# AD_IanFritz_CONTROLS.net
KiCad netlist of a schematic drawn in EAGLE
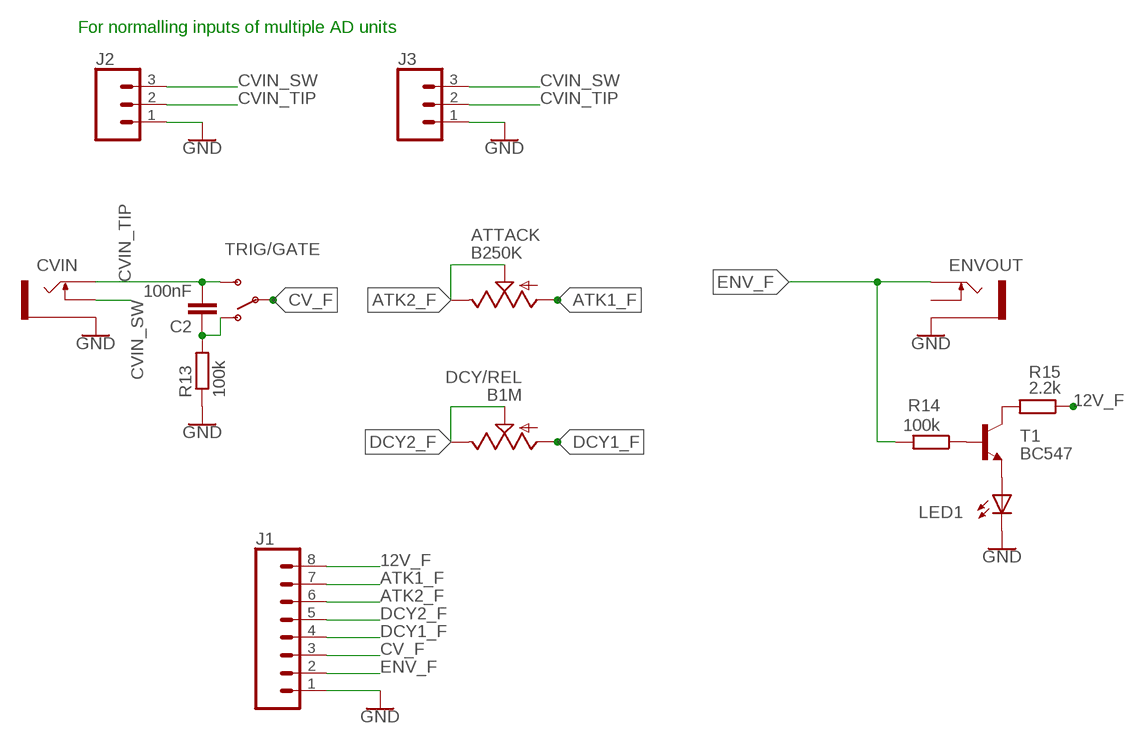
[diagram p0: schematic, sheet 1]

(export (version "E")
  (design (tool "Eeschema 10.0.6"))
  (components
    (comp (ref "ATTACK")
      (value "B250K")
      (footprint "eagle-import:9MM_SNAP-IN_POT")
      (libsource (lib "eagle-import") (part "9MM_SNAP-IN_POT_"))
    )
    (comp (ref "C2")
      (value "100nF")
      (footprint "eagle-import:C2.5-3")
      (libsource (lib "eagle-import") (part "C2,5-3"))
    )
    (comp (ref "CVIN")
      (value "THONKICONNNEW")
      (footprint "eagle-import:WQP-PJ301M-12_JACK")
      (libsource (lib "eagle-import") (part "THONKICONNNEW"))
    )
    (comp (ref "DCY/REL")
      (value "B1M")
      (footprint "eagle-import:9MM_SNAP-IN_POT")
      (libsource (lib "eagle-import") (part "9MM_SNAP-IN_POT_"))
    )
    (comp (ref "ENVOUT")
      (value "THONKICONNNEW")
      (footprint "eagle-import:WQP-PJ301M-12_JACK")
      (libsource (lib "eagle-import") (part "THONKICONNNEW"))
    )
    (comp (ref "J1")
      (value "CONN_08\"")
      (footprint "eagle-import:1X08")
      (libsource (lib "eagle-import") (part "CONN_08{dblquote}"))
    )
    (comp (ref "J2")
      (value "CONN_031X03_NO_SILK")
      (footprint "eagle-import:1X03_NO_SILK")
      (libsource (lib "eagle-import") (part "CONN_031X03_NO_SILK"))
    )
    (comp (ref "J3")
      (value "CONN_031X03_NO_SILK")
      (footprint "eagle-import:1X03_NO_SILK")
      (libsource (lib "eagle-import") (part "CONN_031X03_NO_SILK"))
    )
    (comp (ref "LED1")
      (value "LED3MM")
      (footprint "eagle-import:LED3MM")
      (libsource (lib "eagle-import") (part "LED3MM"))
    )
    (comp (ref "R13")
      (value "100k")
      (footprint "eagle-import:7MM_RESISTOR")
      (libsource (lib "eagle-import") (part "RESISTOR7MM"))
    )
    (comp (ref "R14")
      (value "100k")
      (footprint "eagle-import:7MM_RESISTOR")
      (libsource (lib "eagle-import") (part "RESISTOR7MM"))
    )
    (comp (ref "R15")
      (value "2.2k")
      (footprint "eagle-import:7MM_RESISTOR")
      (libsource (lib "eagle-import") (part "RESISTOR7MM"))
    )
    (comp (ref "T1")
      (value "BC547")
      (footprint "eagle-import:TO92")
      (libsource (lib "eagle-import") (part "BC547"))
    )
    (comp (ref "TRIG/GATE")
      (value "SUBMINI_SPDT")
      (footprint "eagle-import:SUBMINI_TOGGLE")
      (libsource (lib "eagle-import") (part "SUBMINI_SPDT"))
    )
  )
  (nets
    (net (code "1") (name "/12V_F") (class "Default")
      (node (ref "J1") (pin "8") (pinfunction "8_8") (pintype "passive"))
      (node (ref "R15") (pin "1") (pinfunction "1_1") (pintype "passive"))
    )
    (net (code "2") (name "/CVIN_SW") (class "Default")
      (node (ref "CVIN") (pin "P$2_SWITCH") (pinfunction "SWITCH_P$2_SWITCH") (pintype "passive"))
      (node (ref "J2") (pin "3") (pinfunction "3_3") (pintype "passive"))
      (node (ref "J3") (pin "3") (pinfunction "3_3") (pintype "passive"))
    )
    (net (code "3") (name "/CVIN_TIP") (class "Default")
      (node (ref "C2") (pin "2") (pinfunction "2_2") (pintype "passive"))
      (node (ref "CVIN") (pin "P$1_TIP") (pinfunction "TIP_P$1_TIP") (pintype "passive"))
      (node (ref "J2") (pin "2") (pinfunction "2_2") (pintype "passive"))
      (node (ref "J3") (pin "2") (pinfunction "2_2") (pintype "passive"))
      (node (ref "TRIG/GATE") (pin "3") (pinfunction "S_3") (pintype "passive"))
    )
    (net (code "4") (name "ATK1_F") (class "Default")
      (node (ref "ATTACK") (pin "1") (pinfunction "A_1") (pintype "passive"))
      (node (ref "J1") (pin "7") (pinfunction "7_7") (pintype "passive"))
    )
    (net (code "5") (name "ATK2_F") (class "Default")
      (node (ref "ATTACK") (pin "2") (pinfunction "S_2") (pintype "passive"))
      (node (ref "ATTACK") (pin "3") (pinfunction "E_3") (pintype "passive"))
      (node (ref "J1") (pin "6") (pinfunction "6_6") (pintype "passive"))
    )
    (net (code "6") (name "CV_F") (class "Default")
      (node (ref "J1") (pin "3") (pinfunction "3_3") (pintype "passive"))
      (node (ref "TRIG/GATE") (pin "COM") (pinfunction "COMMON_COM") (pintype "passive"))
    )
    (net (code "7") (name "DCY1_F") (class "Default")
      (node (ref "DCY/REL") (pin "1") (pinfunction "A_1") (pintype "passive"))
      (node (ref "J1") (pin "4") (pinfunction "4_4") (pintype "passive"))
    )
    (net (code "8") (name "DCY2_F") (class "Default")
      (node (ref "DCY/REL") (pin "2") (pinfunction "S_2") (pintype "passive"))
      (node (ref "DCY/REL") (pin "3") (pinfunction "E_3") (pintype "passive"))
      (node (ref "J1") (pin "5") (pinfunction "5_5") (pintype "passive"))
    )
    (net (code "9") (name "ENV_F") (class "Default")
      (node (ref "ENVOUT") (pin "P$1_TIP") (pinfunction "TIP_P$1_TIP") (pintype "passive"))
      (node (ref "J1") (pin "2") (pinfunction "2_2") (pintype "passive"))
      (node (ref "R14") (pin "2") (pinfunction "2_2") (pintype "passive"))
    )
    (net (code "10") (name "GND") (class "Default")
      (node (ref "CVIN") (pin "P$3_SLEEVE") (pinfunction "SLEEVE_P$3_SLEEVE") (pintype "passive"))
      (node (ref "ENVOUT") (pin "P$3_SLEEVE") (pinfunction "SLEEVE_P$3_SLEEVE") (pintype "passive"))
      (node (ref "J1") (pin "1") (pinfunction "1_1") (pintype "passive"))
      (node (ref "J2") (pin "1") (pinfunction "1_1") (pintype "passive"))
      (node (ref "J3") (pin "1") (pinfunction "1_1") (pintype "passive"))
      (node (ref "LED1") (pin "K") (pinfunction "C_K") (pintype "passive"))
      (node (ref "R13") (pin "1") (pinfunction "1_1") (pintype "passive"))
    )
    (net (code "11") (name "Net-(T1-B)") (class "Default")
      (node (ref "R14") (pin "1") (pinfunction "1_1") (pintype "passive"))
      (node (ref "T1") (pin "2") (pinfunction "B_2") (pintype "passive"))
    )
    (net (code "12") (name "Net-(T1-C)") (class "Default")
      (node (ref "R15") (pin "2") (pinfunction "2_2") (pintype "passive"))
      (node (ref "T1") (pin "3") (pinfunction "C_3") (pintype "passive"))
    )
    (net (code "13") (name "Net-(T1-E)") (class "Default")
      (node (ref "LED1") (pin "A") (pinfunction "A_A") (pintype "passive"))
      (node (ref "T1") (pin "1") (pinfunction "E_1") (pintype "passive"))
    )
    (net (code "14") (name "Net-(TRIG/GATE-O)") (class "Default")
      (node (ref "C2") (pin "1") (pinfunction "1_1") (pintype "passive"))
      (node (ref "R13") (pin "2") (pinfunction "2_2") (pintype "passive"))
      (node (ref "TRIG/GATE") (pin "1") (pinfunction "O_1") (pintype "passive"))
    )
    (net (code "15") (name "unconnected-(ENVOUT-SWITCH-PadP$2_SWITCH)") (class "Default")
      (node (ref "ENVOUT") (pin "P$2_SWITCH") (pinfunction "SWITCH_P$2_SWITCH") (pintype "passive"))
    )
  )
)
